# LIN-interface.net
KiCad netlist of a schematic drawn in EAGLE
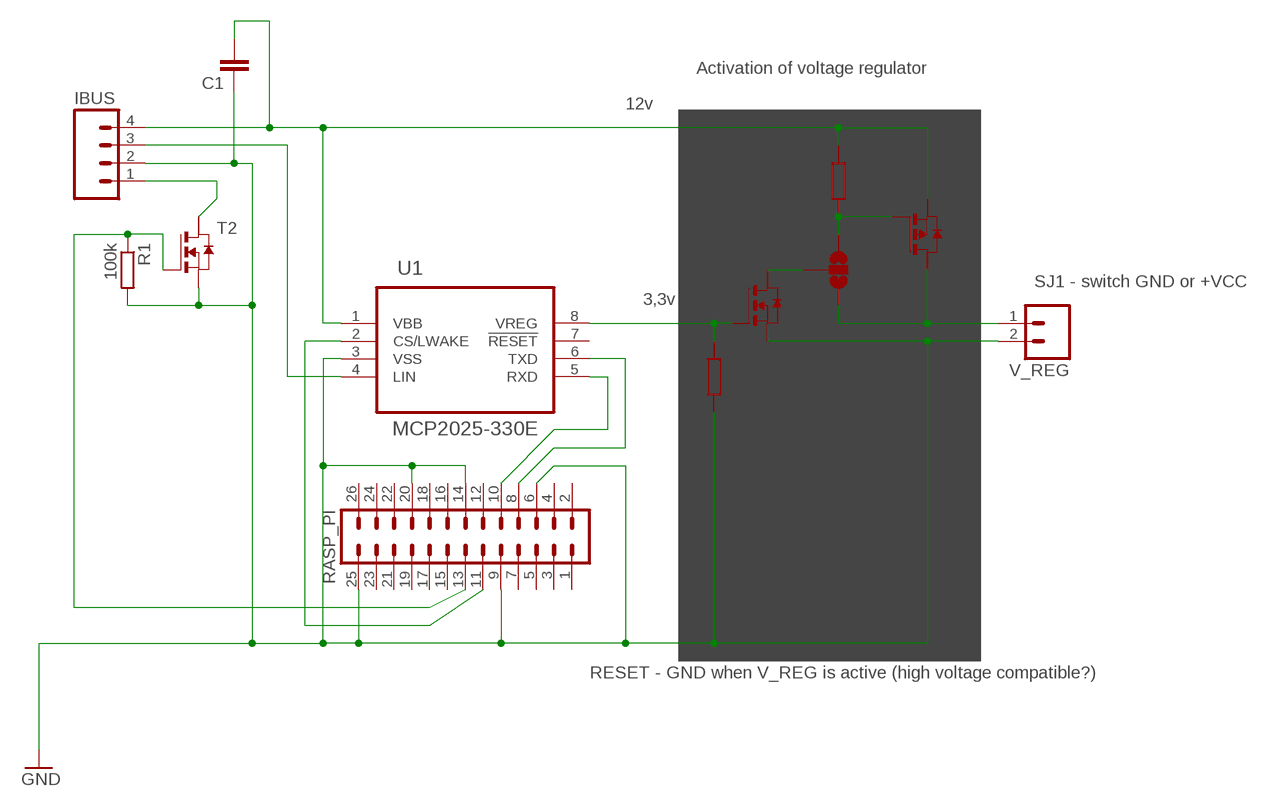
[diagram p0: schematic, sheet 1]

(export (version "E")
  (design (tool "Eeschema 10.0.6"))
  (components
    (comp (ref "C1")
      (value "C-EUC1812")
      (footprint "eagle-import:C1812")
      (libsource (lib "eagle-import") (part "C-EUC1812"))
    )
    (comp (ref "IBUS")
      (value "M04")
      (footprint "eagle-import:04P")
      (libsource (lib "eagle-import") (part "M04"))
    )
    (comp (ref "R1")
      (value "100k")
      (footprint "eagle-import:R5025")
      (libsource (lib "eagle-import") (part "R-EU_R5025"))
    )
    (comp (ref "R2")
      (value "100k")
      (footprint "eagle-import:R5025")
      (libsource (lib "eagle-import") (part "R-EU_R5025"))
    )
    (comp (ref "R3")
      (value "100k")
      (footprint "eagle-import:R5025")
      (libsource (lib "eagle-import") (part "R-EU_R5025"))
    )
    (comp (ref "RASP_PI")
      (value "MA13-2MIRRORED")
      (footprint "eagle-import:ML26-MIRRORED")
      (libsource (lib "eagle-import") (part "MA13-2MIRRORED"))
    )
    (comp (ref "SJ1")
      (value "SJ2W")
      (footprint "eagle-import:SJ_2")
      (libsource (lib "eagle-import") (part "SJ2W"))
    )
    (comp (ref "T1")
      (value "NMOSSOT223")
      (footprint "eagle-import:SOT223")
      (libsource (lib "eagle-import") (part "NMOSSOT223"))
    )
    (comp (ref "T2")
      (value "NMOSSOT223")
      (footprint "eagle-import:SOT223")
      (libsource (lib "eagle-import") (part "NMOSSOT223"))
    )
    (comp (ref "T3")
      (value "PMOSSOT223")
      (footprint "eagle-import:SOT223")
      (libsource (lib "eagle-import") (part "PMOSSOT223"))
    )
    (comp (ref "U1")
      (value "MCP2025-330E")
      (footprint "eagle-import:DIL08")
      (fields (field (name "MPN") "MCP2025-330E/P ") (field (name "PACKAGE") "DIP08"))
      (libsource (lib "eagle-import") (part "MCP2025-330E/PDIP08"))
    )
    (comp (ref "V_REG")
      (value "M02")
      (footprint "eagle-import:02P")
      (libsource (lib "eagle-import") (part "M02"))
    )
  )
  (nets
    (net (code "1") (name "GND") (class "Default")
      (node (ref "C1") (pin "1") (pinfunction "1_1") (pintype "passive"))
      (node (ref "IBUS") (pin "2") (pinfunction "2_2") (pintype "passive"))
      (node (ref "R1") (pin "2") (pinfunction "2_2") (pintype "passive"))
      (node (ref "R2") (pin "2") (pinfunction "2_2") (pintype "passive"))
      (node (ref "RASP_PI") (pin "14") (pinfunction "14_14") (pintype "passive"))
      (node (ref "RASP_PI") (pin "20") (pinfunction "20_20") (pintype "passive"))
      (node (ref "RASP_PI") (pin "25") (pinfunction "25_25") (pintype "passive"))
      (node (ref "RASP_PI") (pin "6") (pinfunction "6_6") (pintype "passive"))
      (node (ref "RASP_PI") (pin "9") (pinfunction "9_9") (pintype "passive"))
      (node (ref "T1") (pin "3") (pinfunction "S_3") (pintype "passive"))
      (node (ref "T2") (pin "3") (pinfunction "S_3") (pintype "passive"))
      (node (ref "U1") (pin "3") (pinfunction "VSS_3") (pintype "power_in"))
      (node (ref "V_REG") (pin "2") (pinfunction "2_2") (pintype "passive"))
    )
    (net (code "2") (name "Net-(T1-D)") (class "Default")
      (node (ref "SJ1") (pin "2") (pinfunction "2_2") (pintype "passive"))
      (node (ref "T1") (pin "2") (pinfunction "D_2") (pintype "passive"))
    )
    (net (code "3") (name "Net-(T1-G)") (class "Default")
      (node (ref "R2") (pin "1") (pinfunction "1_1") (pintype "passive"))
      (node (ref "T1") (pin "1") (pinfunction "G_1") (pintype "passive"))
      (node (ref "U1") (pin "8") (pinfunction "VREG_8") (pintype "output"))
    )
    (net (code "4") (name "Net-(T2-D)") (class "Default")
      (node (ref "IBUS") (pin "1") (pinfunction "1_1") (pintype "passive"))
      (node (ref "T2") (pin "2") (pinfunction "D_2") (pintype "passive"))
    )
    (net (code "5") (name "Net-(T2-G)") (class "Default")
      (node (ref "R1") (pin "1") (pinfunction "1_1") (pintype "passive"))
      (node (ref "RASP_PI") (pin "13") (pinfunction "13_13") (pintype "passive"))
      (node (ref "T2") (pin "1") (pinfunction "G_1") (pintype "passive"))
    )
    (net (code "6") (name "Net-(T3-D)") (class "Default")
      (node (ref "SJ1") (pin "3") (pinfunction "3_3") (pintype "passive"))
      (node (ref "T3") (pin "2") (pinfunction "D_2") (pintype "passive"))
      (node (ref "V_REG") (pin "1") (pinfunction "1_1") (pintype "passive"))
    )
    (net (code "7") (name "Net-(T3-G)") (class "Default")
      (node (ref "R3") (pin "2") (pinfunction "2_2") (pintype "passive"))
      (node (ref "SJ1") (pin "1") (pinfunction "1_1") (pintype "passive"))
      (node (ref "T3") (pin "1") (pinfunction "G_1") (pintype "passive"))
    )
    (net (code "8") (name "Net-(T3-S)") (class "Default")
      (node (ref "C1") (pin "2") (pinfunction "2_2") (pintype "passive"))
      (node (ref "IBUS") (pin "4") (pinfunction "4_4") (pintype "passive"))
      (node (ref "R3") (pin "1") (pinfunction "1_1") (pintype "passive"))
      (node (ref "T3") (pin "3") (pinfunction "S_3") (pintype "passive"))
      (node (ref "U1") (pin "1") (pinfunction "VBB_1") (pintype "power_in"))
    )
    (net (code "9") (name "Net-(U1-CS{slash}LWAKE)") (class "Default")
      (node (ref "RASP_PI") (pin "11") (pinfunction "11_11") (pintype "passive"))
      (node (ref "U1") (pin "2") (pinfunction "CS/LWAKE_2") (pintype "input"))
    )
    (net (code "10") (name "Net-(U1-LIN)") (class "Default")
      (node (ref "IBUS") (pin "3") (pinfunction "3_3") (pintype "passive"))
      (node (ref "U1") (pin "4") (pinfunction "LIN_4") (pintype "bidirectional"))
    )
    (net (code "11") (name "Net-(U1-RXD)") (class "Default")
      (node (ref "RASP_PI") (pin "10") (pinfunction "10_10") (pintype "passive"))
      (node (ref "U1") (pin "5") (pinfunction "RXD_5") (pintype "output"))
    )
    (net (code "12") (name "Net-(U1-TXD)") (class "Default")
      (node (ref "RASP_PI") (pin "8") (pinfunction "8_8") (pintype "passive"))
      (node (ref "U1") (pin "6") (pinfunction "TXD_6") (pintype "input"))
    )
    (net (code "13") (name "unconnected-(RASP_PI-Pad1)") (class "Default")
      (node (ref "RASP_PI") (pin "1") (pinfunction "1_1") (pintype "passive"))
    )
    (net (code "14") (name "unconnected-(RASP_PI-Pad2)") (class "Default")
      (node (ref "RASP_PI") (pin "2") (pinfunction "2_2") (pintype "passive"))
    )
    (net (code "15") (name "unconnected-(RASP_PI-Pad3)") (class "Default")
      (node (ref "RASP_PI") (pin "3") (pinfunction "3_3") (pintype "passive"))
    )
    (net (code "16") (name "unconnected-(RASP_PI-Pad4)") (class "Default")
      (node (ref "RASP_PI") (pin "4") (pinfunction "4_4") (pintype "passive"))
    )
    (net (code "17") (name "unconnected-(RASP_PI-Pad5)") (class "Default")
      (node (ref "RASP_PI") (pin "5") (pinfunction "5_5") (pintype "passive"))
    )
    (net (code "18") (name "unconnected-(RASP_PI-Pad7)") (class "Default")
      (node (ref "RASP_PI") (pin "7") (pinfunction "7_7") (pintype "passive"))
    )
    (net (code "19") (name "unconnected-(RASP_PI-Pad12)") (class "Default")
      (node (ref "RASP_PI") (pin "12") (pinfunction "12_12") (pintype "passive"))
    )
    (net (code "20") (name "unconnected-(RASP_PI-Pad15)") (class "Default")
      (node (ref "RASP_PI") (pin "15") (pinfunction "15_15") (pintype "passive"))
    )
    (net (code "21") (name "unconnected-(RASP_PI-Pad16)") (class "Default")
      (node (ref "RASP_PI") (pin "16") (pinfunction "16_16") (pintype "passive"))
    )
    (net (code "22") (name "unconnected-(RASP_PI-Pad17)") (class "Default")
      (node (ref "RASP_PI") (pin "17") (pinfunction "17_17") (pintype "passive"))
    )
    (net (code "23") (name "unconnected-(RASP_PI-Pad18)") (class "Default")
      (node (ref "RASP_PI") (pin "18") (pinfunction "18_18") (pintype "passive"))
    )
    (net (code "24") (name "unconnected-(RASP_PI-Pad19)") (class "Default")
      (node (ref "RASP_PI") (pin "19") (pinfunction "19_19") (pintype "passive"))
    )
    (net (code "25") (name "unconnected-(RASP_PI-Pad21)") (class "Default")
      (node (ref "RASP_PI") (pin "21") (pinfunction "21_21") (pintype "passive"))
    )
    (net (code "26") (name "unconnected-(RASP_PI-Pad22)") (class "Default")
      (node (ref "RASP_PI") (pin "22") (pinfunction "22_22") (pintype "passive"))
    )
    (net (code "27") (name "unconnected-(RASP_PI-Pad23)") (class "Default")
      (node (ref "RASP_PI") (pin "23") (pinfunction "23_23") (pintype "passive"))
    )
    (net (code "28") (name "unconnected-(RASP_PI-Pad24)") (class "Default")
      (node (ref "RASP_PI") (pin "24") (pinfunction "24_24") (pintype "passive"))
    )
    (net (code "29") (name "unconnected-(RASP_PI-Pad26)") (class "Default")
      (node (ref "RASP_PI") (pin "26") (pinfunction "26_26") (pintype "passive"))
    )
    (net (code "30") (name "unconnected-(T1-D2-Pad4)") (class "Default")
      (node (ref "T1") (pin "4") (pinfunction "D2_4") (pintype "passive"))
    )
    (net (code "31") (name "unconnected-(T2-D2-Pad4)") (class "Default")
      (node (ref "T2") (pin "4") (pinfunction "D2_4") (pintype "passive"))
    )
    (net (code "32") (name "unconnected-(T3-D2-Pad4)") (class "Default")
      (node (ref "T3") (pin "4") (pinfunction "D2_4") (pintype "passive"))
    )
    (net (code "33") (name "unconnected-(U1-~{RESET}-Pad7)") (class "Default")
      (node (ref "U1") (pin "7") (pinfunction "~{RESET}_7") (pintype "output"))
    )
  )
)
